# MainControl.net
KiCad netlist of a schematic drawn in Altium Designer
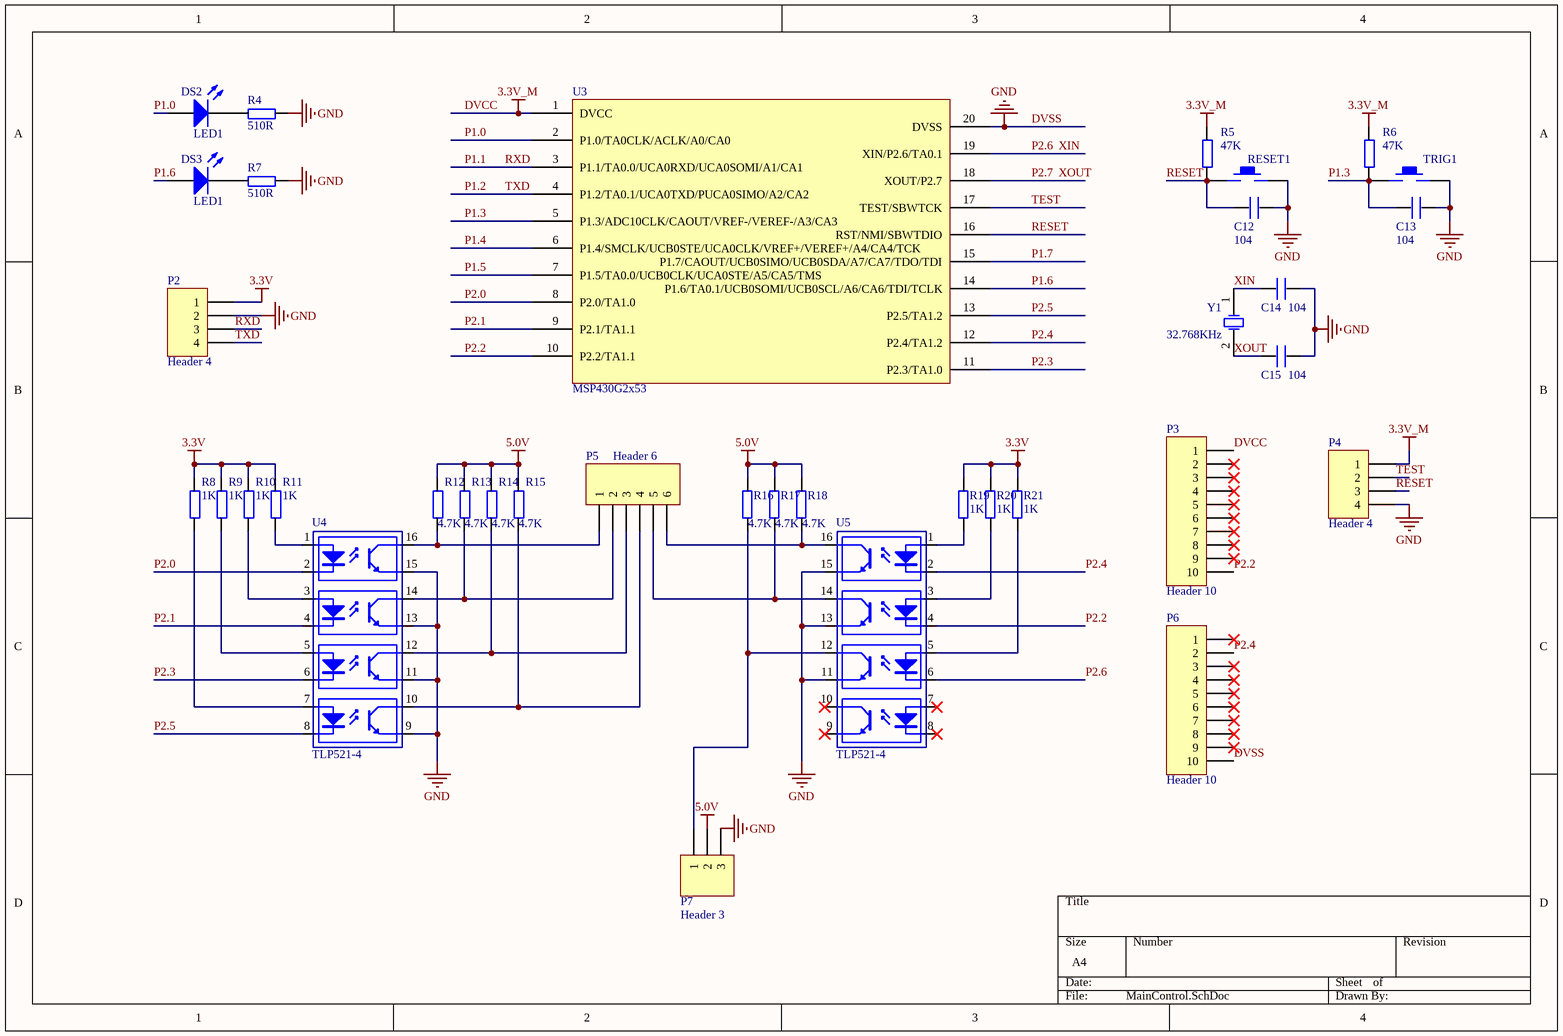
[diagram p0: MainControl.SchDoc]

(export (version "E")
  (design (tool "Eeschema 10.0.6"))
  (components
    (comp (ref "C12") (value "104") (footprint "0603P") (libsource (lib "WarShip V3 STM32103封装库") (part "C")))
    (comp (ref "C13") (value "104") (footprint "0603P") (libsource (lib "WarShip V3 STM32103封装库") (part "C")))
    (comp (ref "C14") (value "104") (footprint "0603P") (libsource (lib "WarShip V3 STM32103封装库") (part "C")))
    (comp (ref "C15") (value "104") (footprint "0603P") (libsource (lib "WarShip V3 STM32103封装库") (part "C")))
    (comp (ref "DS2")
      (value "LED1")
      (footprint "SMDLED")
      (description "Typical RED, GREEN, YELLOW, AMBER GaAs LED")
      (fields (field (name "PUBLISHER") "Altium Limited"))
      (libsource (lib "WarShip V3 STM32103封装库") (part "LED2"))
    )
    (comp (ref "DS3")
      (value "LED1")
      (footprint "SMDLED")
      (description "Typical RED, GREEN, YELLOW, AMBER GaAs LED")
      (fields (field (name "PUBLISHER") "Altium Limited"))
      (libsource (lib "WarShip V3 STM32103封装库") (part "LED2"))
    )
    (comp (ref "P2")
      (value "Header 4")
      (footprint "HDR1X4")
      (description "Header, 4-Pin")
      (fields (field (name "PUBLISHER") "Altium Limited"))
      (libsource (lib "Miscellaneous Connectors") (part "Header 4"))
    )
    (comp (ref "P3")
      (value "Header 10")
      (footprint "HDR1X10")
      (description "Header, 10-Pin")
      (fields (field (name "PUBLISHER") "Altium Limited"))
      (libsource (lib "Miscellaneous Connectors") (part "Header 10"))
    )
    (comp (ref "P4")
      (value "Header 4")
      (footprint "HDR1X4")
      (description "Header, 4-Pin")
      (fields (field (name "PUBLISHER") "Altium Limited"))
      (libsource (lib "Miscellaneous Connectors") (part "Header 4"))
    )
    (comp (ref "P5")
      (value "Header 6")
      (footprint "HDR1X6")
      (description "Header, 6-Pin")
      (fields (field (name "PUBLISHER") "Altium Limited"))
      (libsource (lib "Miscellaneous Connectors") (part "Header 6"))
    )
    (comp (ref "P6")
      (value "Header 10")
      (footprint "HDR1X10")
      (description "Header, 10-Pin")
      (fields (field (name "PUBLISHER") "Altium Limited"))
      (libsource (lib "Miscellaneous Connectors") (part "Header 10"))
    )
    (comp (ref "P7")
      (value "Header 3")
      (footprint "HDR1X3")
      (description "Header, 3-Pin")
      (fields (field (name "PUBLISHER") "Altium Limited"))
      (libsource (lib "Miscellaneous Connectors") (part "Header 3"))
    )
    (comp (ref "R4") (value "510R") (footprint "0603P") (libsource (lib "WarShip V3 STM32103封装库") (part "R")))
    (comp (ref "R5") (value "47K") (footprint "0603P") (libsource (lib "WarShip V3 STM32103封装库") (part "R")))
    (comp (ref "R6") (value "47K") (footprint "0603P") (libsource (lib "WarShip V3 STM32103封装库") (part "R")))
    (comp (ref "R7") (value "510R") (footprint "0603P") (libsource (lib "WarShip V3 STM32103封装库") (part "R")))
    (comp (ref "R8") (value "1K") (footprint "0603P") (libsource (lib "WarShip V3 STM32103封装库") (part "R")))
    (comp (ref "R9") (value "1K") (footprint "0603P") (libsource (lib "WarShip V3 STM32103封装库") (part "R")))
    (comp (ref "R10") (value "1K") (footprint "0603P") (libsource (lib "WarShip V3 STM32103封装库") (part "R")))
    (comp (ref "R11") (value "1K") (footprint "0603P") (libsource (lib "WarShip V3 STM32103封装库") (part "R")))
    (comp (ref "R12")
      (value "4.7K")
      (footprint "0603P")
      (libsource (lib "WarShip V3 STM32103封装库") (part "R"))
    )
    (comp (ref "R13")
      (value "4.7K")
      (footprint "0603P")
      (libsource (lib "WarShip V3 STM32103封装库") (part "R"))
    )
    (comp (ref "R14")
      (value "4.7K")
      (footprint "0603P")
      (libsource (lib "WarShip V3 STM32103封装库") (part "R"))
    )
    (comp (ref "R15")
      (value "4.7K")
      (footprint "0603P")
      (libsource (lib "WarShip V3 STM32103封装库") (part "R"))
    )
    (comp (ref "R16")
      (value "4.7K")
      (footprint "0603P")
      (libsource (lib "WarShip V3 STM32103封装库") (part "R"))
    )
    (comp (ref "R17")
      (value "4.7K")
      (footprint "0603P")
      (libsource (lib "WarShip V3 STM32103封装库") (part "R"))
    )
    (comp (ref "R18")
      (value "4.7K")
      (footprint "0603P")
      (libsource (lib "WarShip V3 STM32103封装库") (part "R"))
    )
    (comp (ref "R19") (value "1K") (footprint "0603P") (libsource (lib "WarShip V3 STM32103封装库") (part "R")))
    (comp (ref "R20") (value "1K") (footprint "0603P") (libsource (lib "WarShip V3 STM32103封装库") (part "R")))
    (comp (ref "R21") (value "1K") (footprint "0603P") (libsource (lib "WarShip V3 STM32103封装库") (part "R")))
    (comp (ref "RESET1")
      (value "KEY_M")
      (footprint "KEY_M")
      (libsource (lib "WarShip V3 STM32103封装库") (part "KEY_M"))
    )
    (comp (ref "TRIG1")
      (value "KEY_M")
      (footprint "KEY_M")
      (libsource (lib "WarShip V3 STM32103封装库") (part "KEY_M"))
    )
    (comp (ref "U3")
      (value "MSP430G2x53")
      (footprint "MSP430G2x53")
      (description "MSP430G2x53 microcontrollers")
      (libsource (lib "Zink_LIB") (part "MSP430G2x53"))
    )
    (comp (ref "U4")
      (value "TLP521-4")
      (footprint "DIP16")
      (description "4 x 4-Pin Phototransistor Optocoupler")
      (fields (field (name "PUBLISHER") "Altium Limited"))
      (libsource (lib "Zink_LIB") (part "TLP521-4"))
    )
    (comp (ref "U5")
      (value "TLP521-4")
      (footprint "DIP16")
      (description "4 x 4-Pin Phototransistor Optocoupler")
      (fields (field (name "PUBLISHER") "Altium Limited"))
      (libsource (lib "Zink_LIB") (part "TLP521-4"))
    )
    (comp (ref "Y1")
      (value "32.768KHz")
      (footprint "XTAL32")
      (description "Crystal Oscillator")
      (fields (field (name "PUBLISHER") "Altium Limited"))
      (libsource (lib "WarShip V3 STM32103封装库") (part "XTAL"))
    )
  )
  (nets
    (net (code "1") (name "/P1.0") (class "Default")
      (node (ref "DS2") (pin "1") (pinfunction "A_1") (pintype "passive"))
      (node (ref "U3") (pin "2") (pinfunction "P1.0/TA0CLK/ACLK/A0/CA0_2") (pintype "passive"))
    )
    (net (code "2") (name "/P1.1") (class "Default")
      (node (ref "P2") (pin "3") (pinfunction "3_3") (pintype "passive"))
      (node (ref "U3") (pin "3") (pinfunction "P1.1/TA0.0/UCA0RXD/UCA0SOMI/A1/CA1_3") (pintype "passive"))
    )
    (net (code "3") (name "/P1.2") (class "Default")
      (node (ref "P2") (pin "4") (pinfunction "4_4") (pintype "passive"))
      (node (ref "U3") (pin "4") (pinfunction "P1.2/TA0.1/UCA0TXD/PUCA0SIMO/A2/CA2_4") (pintype "passive"))
    )
    (net (code "4") (name "/P1.3") (class "Default")
      (node (ref "C13") (pin "2") (pintype "passive"))
      (node (ref "R6") (pin "1") (pintype "passive"))
      (node (ref "TRIG1") (pin "1") (pinfunction "1_1") (pintype "passive"))
      (node (ref "U3") (pin "5") (pinfunction "P1.3/ADC10CLK/CAOUT/VREF-/VEREF-/A3/CA3_5") (pintype "passive"))
    )
    (net (code "5") (name "/P1.4") (class "Default")
      (node (ref "U3") (pin "6") (pinfunction "P1.4/SMCLK/UCB0STE/UCA0CLK/VREF+/VEREF+/A4/CA4/TCK_6") (pintype "passive"))
    )
    (net (code "6") (name "/P1.5") (class "Default")
      (node (ref "U3") (pin "7") (pinfunction "P1.5/TA0.0/UCB0CLK/UCA0STE/A5/CA5/TMS_7") (pintype "passive"))
    )
    (net (code "7") (name "/P1.6") (class "Default")
      (node (ref "DS3") (pin "1") (pinfunction "A_1") (pintype "passive"))
      (node (ref "U3") (pin "14") (pinfunction "P1.6/TA0.1/UCB0SOMI/UCB0SCL/A6/CA6/TDI/TCLK_14") (pintype "passive"))
    )
    (net (code "8") (name "/P1.7") (class "Default")
      (node (ref "U3") (pin "15") (pinfunction "P1.7/CAOUT/UCB0SIMO/UCB0SDA/A7/CA7/TDO/TDI_15") (pintype "passive"))
    )
    (net (code "9") (name "/P2.0") (class "Default")
      (node (ref "U3") (pin "8") (pinfunction "P2.0/TA1.0_8") (pintype "passive"))
      (node (ref "U4") (pin "2") (pinfunction "K_2") (pintype "passive"))
    )
    (net (code "10") (name "/P2.1") (class "Default")
      (node (ref "U3") (pin "9") (pinfunction "P2.1/TA1.1_9") (pintype "passive"))
      (node (ref "U4") (pin "4") (pinfunction "K_4") (pintype "passive"))
    )
    (net (code "11") (name "/P2.2") (class "Default")
      (node (ref "P3") (pin "10") (pinfunction "10_10") (pintype "passive"))
      (node (ref "U3") (pin "10") (pinfunction "P2.2/TA1.1_10") (pintype "passive"))
      (node (ref "U5") (pin "4") (pinfunction "K_4") (pintype "passive"))
    )
    (net (code "12") (name "/P2.3") (class "Default")
      (node (ref "U3") (pin "11") (pinfunction "P2.3/TA1.0_11") (pintype "passive"))
      (node (ref "U4") (pin "6") (pinfunction "K_6") (pintype "passive"))
    )
    (net (code "13") (name "/P2.4") (class "Default")
      (node (ref "P6") (pin "2") (pinfunction "2_2") (pintype "passive"))
      (node (ref "U3") (pin "12") (pinfunction "P2.4/TA1.2_12") (pintype "passive"))
      (node (ref "U5") (pin "2") (pinfunction "K_2") (pintype "passive"))
    )
    (net (code "14") (name "/P2.5") (class "Default")
      (node (ref "U3") (pin "13") (pinfunction "P2.5/TA1.2_13") (pintype "passive"))
      (node (ref "U4") (pin "8") (pinfunction "K_8") (pintype "passive"))
    )
    (net (code "15") (name "/P2.6") (class "Default")
      (node (ref "C14") (pin "1") (pintype "passive"))
      (node (ref "U3") (pin "19") (pinfunction "XIN/P2.6/TA0.1_19") (pintype "passive"))
      (node (ref "U5") (pin "6") (pinfunction "K_6") (pintype "passive"))
      (node (ref "Y1") (pin "1") (pinfunction "OSC1_1") (pintype "passive"))
    )
    (net (code "16") (name "/P2.7") (class "Default")
      (node (ref "C15") (pin "1") (pintype "passive"))
      (node (ref "U3") (pin "18") (pinfunction "XOUT/P2.7_18") (pintype "passive"))
      (node (ref "Y1") (pin "2") (pinfunction "OSC2_2") (pintype "passive"))
    )
    (net (code "17") (name "/RESET") (class "Default")
      (node (ref "C12") (pin "2") (pintype "passive"))
      (node (ref "P4") (pin "3") (pinfunction "3_3") (pintype "passive"))
      (node (ref "R5") (pin "1") (pintype "passive"))
      (node (ref "RESET1") (pin "1") (pinfunction "1_1") (pintype "passive"))
      (node (ref "U3") (pin "16") (pinfunction "RST/NMI/SBWTDIO_16") (pintype "passive"))
    )
    (net (code "18") (name "/TEST") (class "Default")
      (node (ref "P4") (pin "2") (pinfunction "2_2") (pintype "passive"))
      (node (ref "U3") (pin "17") (pinfunction "TEST/SBWTCK_17") (pintype "passive"))
    )
    (net (code "19") (name "3.3V") (class "Default")
      (node (ref "P2") (pin "1") (pinfunction "1_1") (pintype "passive"))
      (node (ref "R10") (pin "2") (pintype "passive"))
      (node (ref "R11") (pin "2") (pintype "passive"))
      (node (ref "R19") (pin "2") (pintype "passive"))
      (node (ref "R20") (pin "2") (pintype "passive"))
      (node (ref "R21") (pin "2") (pintype "passive"))
      (node (ref "R8") (pin "2") (pintype "passive"))
      (node (ref "R9") (pin "2") (pintype "passive"))
    )
    (net (code "20") (name "3.3V_M") (class "Default")
      (node (ref "P3") (pin "1") (pinfunction "1_1") (pintype "passive"))
      (node (ref "P4") (pin "1") (pinfunction "1_1") (pintype "passive"))
      (node (ref "R5") (pin "2") (pintype "passive"))
      (node (ref "R6") (pin "2") (pintype "passive"))
      (node (ref "U3") (pin "1") (pinfunction "DVCC_1") (pintype "passive"))
    )
    (net (code "21") (name "5.0V") (class "Default")
      (node (ref "P7") (pin "2") (pinfunction "2_2") (pintype "passive"))
      (node (ref "R12") (pin "2") (pintype "passive"))
      (node (ref "R13") (pin "2") (pintype "passive"))
      (node (ref "R14") (pin "2") (pintype "passive"))
      (node (ref "R15") (pin "2") (pintype "passive"))
      (node (ref "R16") (pin "2") (pintype "passive"))
      (node (ref "R17") (pin "2") (pintype "passive"))
      (node (ref "R18") (pin "2") (pintype "passive"))
    )
    (net (code "22") (name "GND") (class "Default")
      (node (ref "C12") (pin "1") (pintype "passive"))
      (node (ref "C13") (pin "1") (pintype "passive"))
      (node (ref "C14") (pin "2") (pintype "passive"))
      (node (ref "C15") (pin "2") (pintype "passive"))
      (node (ref "P2") (pin "2") (pinfunction "2_2") (pintype "passive"))
      (node (ref "P4") (pin "4") (pinfunction "4_4") (pintype "passive"))
      (node (ref "P6") (pin "10") (pinfunction "10_10") (pintype "passive"))
      (node (ref "P7") (pin "3") (pinfunction "3_3") (pintype "passive"))
      (node (ref "R4") (pin "2") (pintype "passive"))
      (node (ref "R7") (pin "2") (pintype "passive"))
      (node (ref "RESET1") (pin "2") (pinfunction "2_2") (pintype "passive"))
      (node (ref "TRIG1") (pin "2") (pinfunction "2_2") (pintype "passive"))
      (node (ref "U3") (pin "20") (pinfunction "DVSS_20") (pintype "passive"))
      (node (ref "U4") (pin "11") (pinfunction "E_11") (pintype "passive"))
      (node (ref "U4") (pin "13") (pinfunction "E_13") (pintype "passive"))
      (node (ref "U4") (pin "15") (pinfunction "E_15") (pintype "passive"))
      (node (ref "U4") (pin "9") (pinfunction "E_9") (pintype "passive"))
      (node (ref "U5") (pin "11") (pinfunction "E_11") (pintype "passive"))
      (node (ref "U5") (pin "13") (pinfunction "E_13") (pintype "passive"))
      (node (ref "U5") (pin "15") (pinfunction "E_15") (pintype "passive"))
    )
    (net (code "23") (name "Net-(DS2-K)") (class "Default")
      (node (ref "DS2") (pin "2") (pinfunction "K_2") (pintype "passive"))
      (node (ref "R4") (pin "1") (pintype "passive"))
    )
    (net (code "24") (name "Net-(DS3-K)") (class "Default")
      (node (ref "DS3") (pin "2") (pinfunction "K_2") (pintype "passive"))
      (node (ref "R7") (pin "1") (pintype "passive"))
    )
    (net (code "25") (name "Net-(P5-Pad1)") (class "Default")
      (node (ref "P5") (pin "1") (pinfunction "1_1") (pintype "passive"))
      (node (ref "R12") (pin "1") (pintype "passive"))
      (node (ref "U4") (pin "16") (pinfunction "C_16") (pintype "passive"))
    )
    (net (code "26") (name "Net-(P5-Pad2)") (class "Default")
      (node (ref "P5") (pin "2") (pinfunction "2_2") (pintype "passive"))
      (node (ref "R13") (pin "1") (pintype "passive"))
      (node (ref "U4") (pin "14") (pinfunction "C_14") (pintype "passive"))
    )
    (net (code "27") (name "Net-(P5-Pad3)") (class "Default")
      (node (ref "P5") (pin "3") (pinfunction "3_3") (pintype "passive"))
      (node (ref "R14") (pin "1") (pintype "passive"))
      (node (ref "U4") (pin "12") (pinfunction "C_12") (pintype "passive"))
    )
    (net (code "28") (name "Net-(P5-Pad4)") (class "Default")
      (node (ref "P5") (pin "4") (pinfunction "4_4") (pintype "passive"))
      (node (ref "R15") (pin "1") (pintype "passive"))
      (node (ref "U4") (pin "10") (pinfunction "C_10") (pintype "passive"))
    )
    (net (code "29") (name "Net-(P5-Pad5)") (class "Default")
      (node (ref "P5") (pin "5") (pinfunction "5_5") (pintype "passive"))
      (node (ref "R17") (pin "1") (pintype "passive"))
      (node (ref "U5") (pin "14") (pinfunction "C_14") (pintype "passive"))
    )
    (net (code "30") (name "Net-(P5-Pad6)") (class "Default")
      (node (ref "P5") (pin "6") (pinfunction "6_6") (pintype "passive"))
      (node (ref "R18") (pin "1") (pintype "passive"))
      (node (ref "U5") (pin "16") (pinfunction "C_16") (pintype "passive"))
    )
    (net (code "31") (name "Net-(P7-Pad1)") (class "Default")
      (node (ref "P7") (pin "1") (pinfunction "1_1") (pintype "passive"))
      (node (ref "R16") (pin "1") (pintype "passive"))
      (node (ref "U5") (pin "12") (pinfunction "C_12") (pintype "passive"))
    )
    (net (code "32") (name "Net-(R8-Pad1)") (class "Default")
      (node (ref "R8") (pin "1") (pintype "passive"))
      (node (ref "U4") (pin "7") (pinfunction "A_7") (pintype "passive"))
    )
    (net (code "33") (name "Net-(R9-Pad1)") (class "Default")
      (node (ref "R9") (pin "1") (pintype "passive"))
      (node (ref "U4") (pin "5") (pinfunction "A_5") (pintype "passive"))
    )
    (net (code "34") (name "Net-(R10-Pad1)") (class "Default")
      (node (ref "R10") (pin "1") (pintype "passive"))
      (node (ref "U4") (pin "3") (pinfunction "A_3") (pintype "passive"))
    )
    (net (code "35") (name "Net-(R11-Pad1)") (class "Default")
      (node (ref "R11") (pin "1") (pintype "passive"))
      (node (ref "U4") (pin "1") (pinfunction "A_1") (pintype "passive"))
    )
    (net (code "36") (name "Net-(R19-Pad1)") (class "Default")
      (node (ref "R19") (pin "1") (pintype "passive"))
      (node (ref "U5") (pin "1") (pinfunction "A_1") (pintype "passive"))
    )
    (net (code "37") (name "Net-(R20-Pad1)") (class "Default")
      (node (ref "R20") (pin "1") (pintype "passive"))
      (node (ref "U5") (pin "3") (pinfunction "A_3") (pintype "passive"))
    )
    (net (code "38") (name "Net-(R21-Pad1)") (class "Default")
      (node (ref "R21") (pin "1") (pintype "passive"))
      (node (ref "U5") (pin "5") (pinfunction "A_5") (pintype "passive"))
    )
    (net (code "39") (name "unconnected-(P3-Pad2)") (class "Default")
      (node (ref "P3") (pin "2") (pinfunction "2_2") (pintype "passive+no_connect"))
    )
    (net (code "40") (name "unconnected-(P3-Pad3)") (class "Default")
      (node (ref "P3") (pin "3") (pinfunction "3_3") (pintype "passive+no_connect"))
    )
    (net (code "41") (name "unconnected-(P3-Pad4)") (class "Default")
      (node (ref "P3") (pin "4") (pinfunction "4_4") (pintype "passive+no_connect"))
    )
    (net (code "42") (name "unconnected-(P3-Pad5)") (class "Default")
      (node (ref "P3") (pin "5") (pinfunction "5_5") (pintype "passive+no_connect"))
    )
    (net (code "43") (name "unconnected-(P3-Pad6)") (class "Default")
      (node (ref "P3") (pin "6") (pinfunction "6_6") (pintype "passive+no_connect"))
    )
    (net (code "44") (name "unconnected-(P3-Pad7)") (class "Default")
      (node (ref "P3") (pin "7") (pinfunction "7_7") (pintype "passive+no_connect"))
    )
    (net (code "45") (name "unconnected-(P3-Pad8)") (class "Default")
      (node (ref "P3") (pin "8") (pinfunction "8_8") (pintype "passive+no_connect"))
    )
    (net (code "46") (name "unconnected-(P3-Pad9)") (class "Default")
      (node (ref "P3") (pin "9") (pinfunction "9_9") (pintype "passive+no_connect"))
    )
    (net (code "47") (name "unconnected-(P6-Pad1)") (class "Default")
      (node (ref "P6") (pin "1") (pinfunction "1_1") (pintype "passive+no_connect"))
    )
    (net (code "48") (name "unconnected-(P6-Pad3)") (class "Default")
      (node (ref "P6") (pin "3") (pinfunction "3_3") (pintype "passive+no_connect"))
    )
    (net (code "49") (name "unconnected-(P6-Pad4)") (class "Default")
      (node (ref "P6") (pin "4") (pinfunction "4_4") (pintype "passive+no_connect"))
    )
    (net (code "50") (name "unconnected-(P6-Pad5)") (class "Default")
      (node (ref "P6") (pin "5") (pinfunction "5_5") (pintype "passive+no_connect"))
    )
    (net (code "51") (name "unconnected-(P6-Pad6)") (class "Default")
      (node (ref "P6") (pin "6") (pinfunction "6_6") (pintype "passive+no_connect"))
    )
    (net (code "52") (name "unconnected-(P6-Pad7)") (class "Default")
      (node (ref "P6") (pin "7") (pinfunction "7_7") (pintype "passive+no_connect"))
    )
    (net (code "53") (name "unconnected-(P6-Pad8)") (class "Default")
      (node (ref "P6") (pin "8") (pinfunction "8_8") (pintype "passive+no_connect"))
    )
    (net (code "54") (name "unconnected-(P6-Pad9)") (class "Default")
      (node (ref "P6") (pin "9") (pinfunction "9_9") (pintype "passive+no_connect"))
    )
    (net (code "55") (name "unconnected-(U5-A-Pad7)") (class "Default")
      (node (ref "U5") (pin "7") (pinfunction "A_7") (pintype "passive+no_connect"))
    )
    (net (code "56") (name "unconnected-(U5-C-Pad10)") (class "Default")
      (node (ref "U5") (pin "10") (pinfunction "C_10") (pintype "passive+no_connect"))
    )
    (net (code "57") (name "unconnected-(U5-E-Pad9)") (class "Default")
      (node (ref "U5") (pin "9") (pinfunction "E_9") (pintype "passive+no_connect"))
    )
    (net (code "58") (name "unconnected-(U5-K-Pad8)") (class "Default")
      (node (ref "U5") (pin "8") (pinfunction "K_8") (pintype "passive+no_connect"))
    )
  )
)
